# Doorbell.net
KiCad netlist of a schematic drawn in EAGLE
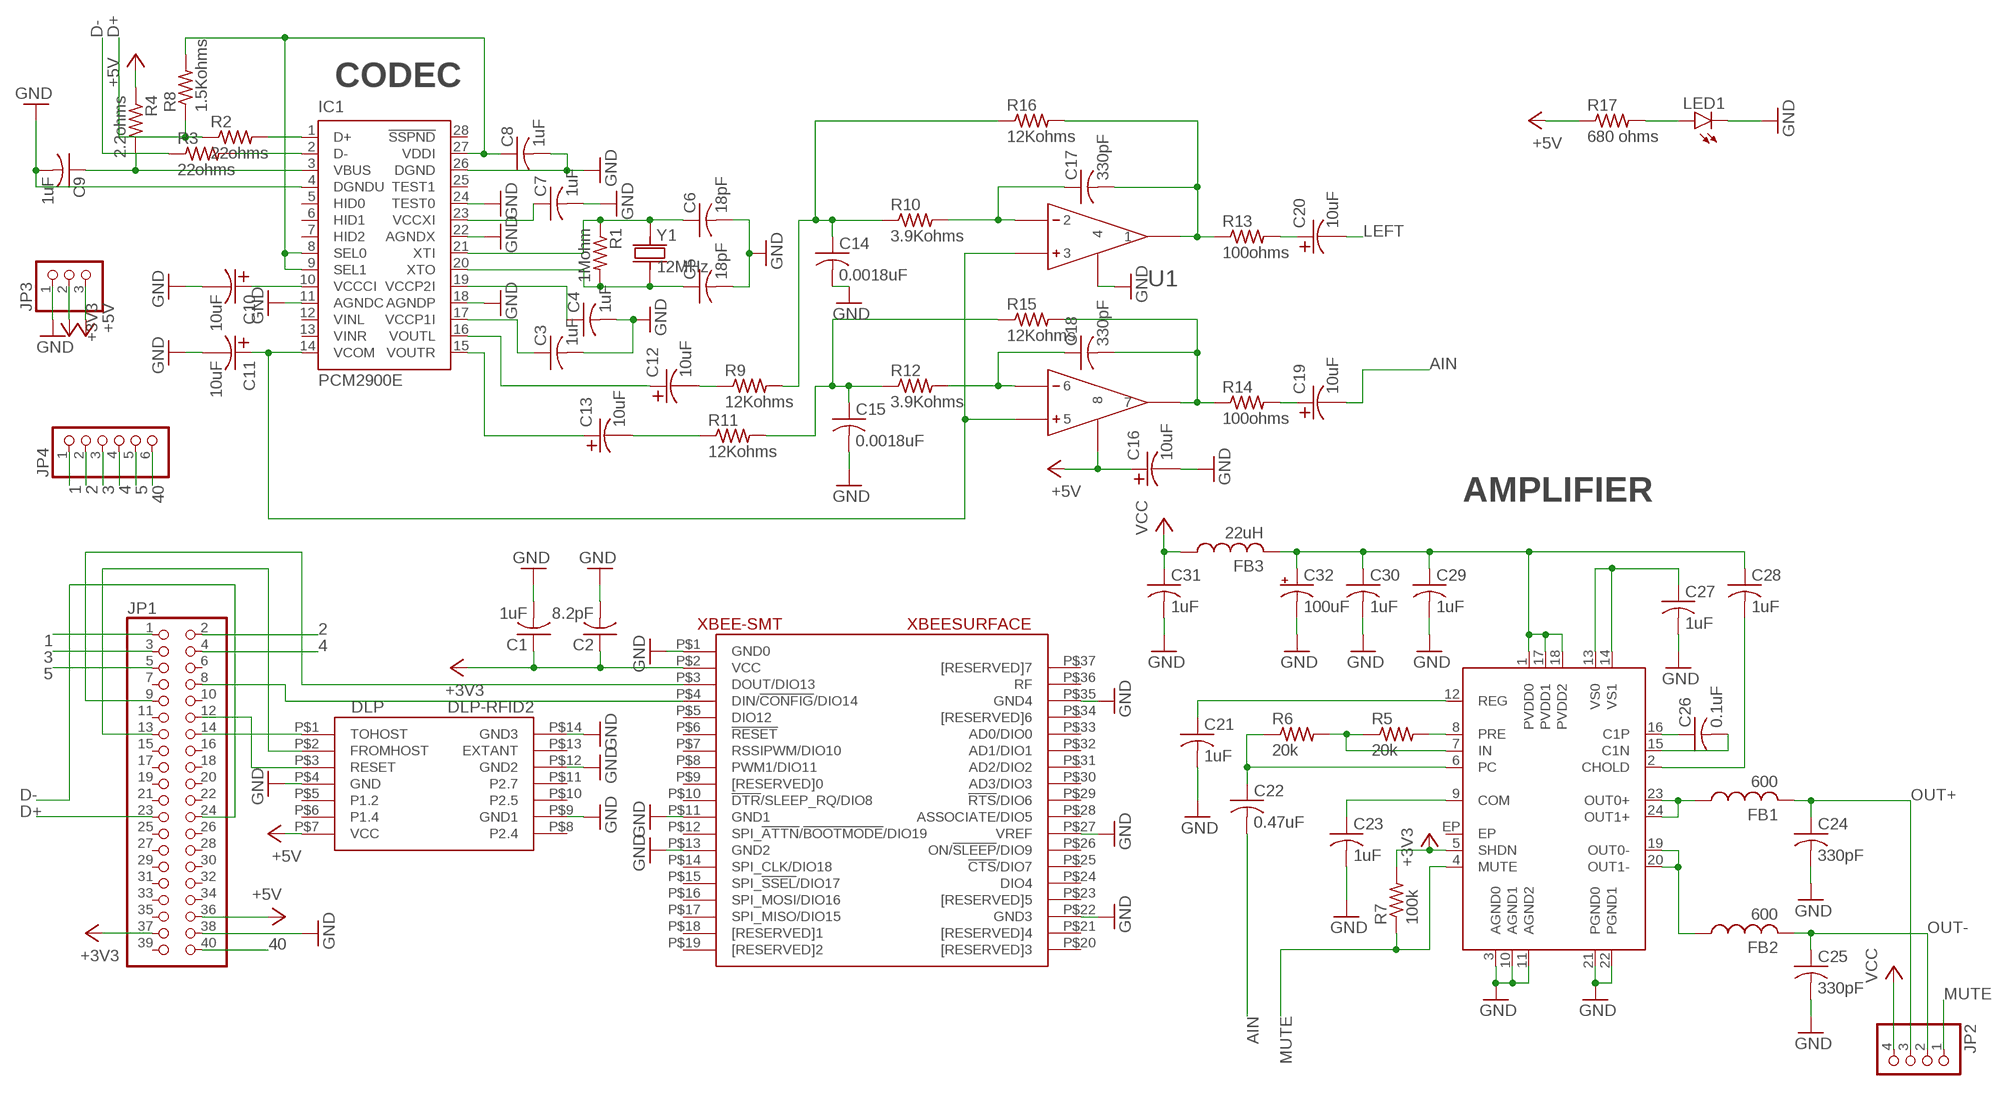
[diagram p0: schematic, sheet 1]

(export (version "E")
  (design (tool "Eeschema 10.0.6"))
  (components
    (comp (ref "C1")
      (value "1uF")
      (footprint "eagle-import:0603_CAP")
      (libsource (lib "eagle-import") (part "CAP0603"))
    )
    (comp (ref "C2")
      (value "8.2pF")
      (footprint "eagle-import:0603_CAP")
      (libsource (lib "eagle-import") (part "CAP0603"))
    )
    (comp (ref "C3")
      (value "1uF")
      (footprint "eagle-import:0603_CAP")
      (libsource (lib "eagle-import") (part "CAP0603"))
    )
    (comp (ref "C4")
      (value "1uF")
      (footprint "eagle-import:0603_CAP")
      (libsource (lib "eagle-import") (part "CAP0603"))
    )
    (comp (ref "C5")
      (value "18pF")
      (footprint "eagle-import:0603_CAP")
      (libsource (lib "eagle-import") (part "CAP0603"))
    )
    (comp (ref "C6")
      (value "18pF")
      (footprint "eagle-import:0603_CAP")
      (libsource (lib "eagle-import") (part "CAP0603"))
    )
    (comp (ref "C7")
      (value "1uF")
      (footprint "eagle-import:0603_CAP")
      (libsource (lib "eagle-import") (part "CAP0603"))
    )
    (comp (ref "C8")
      (value "1uF")
      (footprint "eagle-import:0603_CAP")
      (libsource (lib "eagle-import") (part "CAP0603"))
    )
    (comp (ref "C9")
      (value "1uF")
      (footprint "eagle-import:0603_CAP")
      (libsource (lib "eagle-import") (part "CAP0603"))
    )
    (comp (ref "C10")
      (value "10uF")
      (footprint "eagle-import:1411_CAP")
      (libsource (lib "eagle-import") (part "CAP-TANT"))
    )
    (comp (ref "C11")
      (value "10uF")
      (footprint "eagle-import:1411_CAP")
      (libsource (lib "eagle-import") (part "CAP-TANT"))
    )
    (comp (ref "C12")
      (value "10uF")
      (footprint "eagle-import:1411_CAP")
      (libsource (lib "eagle-import") (part "CAP-TANT"))
    )
    (comp (ref "C13")
      (value "10uF")
      (footprint "eagle-import:1411_CAP")
      (libsource (lib "eagle-import") (part "CAP-TANT"))
    )
    (comp (ref "C14")
      (value "0.0018uF")
      (footprint "eagle-import:0603_CAP")
      (libsource (lib "eagle-import") (part "CAP0603"))
    )
    (comp (ref "C15")
      (value "0.0018uF")
      (footprint "eagle-import:0603_CAP")
      (libsource (lib "eagle-import") (part "CAP0603"))
    )
    (comp (ref "C16")
      (value "10uF")
      (footprint "eagle-import:1411_CAP")
      (libsource (lib "eagle-import") (part "CAP-TANT"))
    )
    (comp (ref "C17")
      (value "330pF")
      (footprint "eagle-import:0603_CAP")
      (libsource (lib "eagle-import") (part "CAP0603"))
    )
    (comp (ref "C18")
      (value "330pF")
      (footprint "eagle-import:0603_CAP")
      (libsource (lib "eagle-import") (part "CAP0603"))
    )
    (comp (ref "C19")
      (value "10uF")
      (footprint "eagle-import:1411_CAP")
      (libsource (lib "eagle-import") (part "CAP-TANT"))
    )
    (comp (ref "C20")
      (value "10uF")
      (footprint "eagle-import:1411_CAP")
      (libsource (lib "eagle-import") (part "CAP-TANT"))
    )
    (comp (ref "C21")
      (value "1uF")
      (footprint "eagle-import:0603_CAP")
      (libsource (lib "eagle-import") (part "CAP0603"))
    )
    (comp (ref "C22")
      (value "0.47uF")
      (footprint "eagle-import:0603_CAP")
      (libsource (lib "eagle-import") (part "CAP0603"))
    )
    (comp (ref "C23")
      (value "1uF")
      (footprint "eagle-import:0603_CAP")
      (libsource (lib "eagle-import") (part "CAP0603"))
    )
    (comp (ref "C24")
      (value "330pF")
      (footprint "eagle-import:0603_CAP")
      (libsource (lib "eagle-import") (part "CAP0603"))
    )
    (comp (ref "C25")
      (value "330pF")
      (footprint "eagle-import:0603_CAP")
      (libsource (lib "eagle-import") (part "CAP0603"))
    )
    (comp (ref "C26")
      (value "0.1uF")
      (footprint "eagle-import:0603_CAP")
      (libsource (lib "eagle-import") (part "CAP0603"))
    )
    (comp (ref "C27")
      (value "1uF")
      (footprint "eagle-import:0603_CAP")
      (libsource (lib "eagle-import") (part "CAP0603"))
    )
    (comp (ref "C28")
      (value "1uF")
      (footprint "eagle-import:0603_CAP")
      (libsource (lib "eagle-import") (part "CAP0603"))
    )
    (comp (ref "C29")
      (value "1uF")
      (footprint "eagle-import:0603_CAP")
      (libsource (lib "eagle-import") (part "CAP0603"))
    )
    (comp (ref "C30")
      (value "1uF")
      (footprint "eagle-import:0603_CAP")
      (libsource (lib "eagle-import") (part "CAP0603"))
    )
    (comp (ref "C31")
      (value "1uF")
      (footprint "eagle-import:0603_CAP")
      (libsource (lib "eagle-import") (part "CAP0603"))
    )
    (comp (ref "C32")
      (value "100uF")
      (footprint "eagle-import:F_CAP")
      (libsource (lib "eagle-import") (part "CAP_POLF"))
    )
    (comp (ref "DLP")
      (value "DLP-RFID2")
      (footprint "eagle-import:DLP-RFID2")
      (libsource (lib "eagle-import") (part "DLP-RFID2"))
    )
    (comp (ref "FB1")
      (value "600")
      (footprint "eagle-import:0805_FB")
      (libsource (lib "eagle-import") (part "FB0805"))
    )
    (comp (ref "FB2")
      (value "600")
      (footprint "eagle-import:0805_FB")
      (libsource (lib "eagle-import") (part "FB0805"))
    )
    (comp (ref "FB3")
      (value "22uH")
      (footprint "eagle-import:0805_FB")
      (libsource (lib "eagle-import") (part "FB0805"))
    )
    (comp (ref "IC1")
      (value "PCM2900E")
      (footprint "eagle-import:SSOP28DB")
      (fields (field (name "MF") "TEXAS INSTRUMENTS"))
      (libsource (lib "eagle-import") (part "PCM2900E"))
    )
    (comp (ref "IC2")
      (value "MAX9737")
      (footprint "eagle-import:TQFN24")
      (fields (field (name "MANF") "Maxim"))
      (libsource (lib "eagle-import") (part "MAX9737"))
    )
    (comp (ref "JP1")
      (value "PINHD-2X20")
      (footprint "eagle-import:2X20")
      (libsource (lib "eagle-import") (part "PINHD-2X20"))
    )
    (comp (ref "JP2")
      (value "PINHD-1X4")
      (footprint "eagle-import:1X04")
      (libsource (lib "eagle-import") (part "PINHD-1X4"))
    )
    (comp (ref "JP3")
      (value "PINHD-1X3")
      (footprint "eagle-import:1X03")
      (libsource (lib "eagle-import") (part "PINHD-1X3"))
    )
    (comp (ref "JP4")
      (value "PINHD-1X6")
      (footprint "eagle-import:1X06")
      (libsource (lib "eagle-import") (part "PINHD-1X6"))
    )
    (comp (ref "LED1")
      (value "LED0603")
      (footprint "eagle-import:0603_LED")
      (fields (field (name "MANF") "Avago Technologies"))
      (libsource (lib "eagle-import") (part "LED0603"))
    )
    (comp (ref "R1")
      (value "1Mohm")
      (footprint "eagle-import:0603_RESISTOR")
      (libsource (lib "eagle-import") (part "RESISTOR0603"))
    )
    (comp (ref "R2")
      (value "22ohms")
      (footprint "eagle-import:0603_RESISTOR")
      (libsource (lib "eagle-import") (part "RESISTOR0603"))
    )
    (comp (ref "R3")
      (value "22ohms")
      (footprint "eagle-import:0603_RESISTOR")
      (libsource (lib "eagle-import") (part "RESISTOR0603"))
    )
    (comp (ref "R4")
      (value "2.2ohms")
      (footprint "eagle-import:0603_RESISTOR")
      (libsource (lib "eagle-import") (part "RESISTOR0603"))
    )
    (comp (ref "R5")
      (value "20k")
      (footprint "eagle-import:0603_RESISTOR")
      (libsource (lib "eagle-import") (part "RESISTOR0603"))
    )
    (comp (ref "R6")
      (value "20k")
      (footprint "eagle-import:0603_RESISTOR")
      (libsource (lib "eagle-import") (part "RESISTOR0603"))
    )
    (comp (ref "R7")
      (value "100k")
      (footprint "eagle-import:0603_RESISTOR")
      (libsource (lib "eagle-import") (part "RESISTOR0603"))
    )
    (comp (ref "R8")
      (value "1.5Kohms")
      (footprint "eagle-import:0603_RESISTOR")
      (libsource (lib "eagle-import") (part "RESISTOR0603"))
    )
    (comp (ref "R9")
      (value "12Kohms")
      (footprint "eagle-import:0603_RESISTOR")
      (libsource (lib "eagle-import") (part "RESISTOR0603"))
    )
    (comp (ref "R10")
      (value "3.9Kohms")
      (footprint "eagle-import:0603_RESISTOR")
      (libsource (lib "eagle-import") (part "RESISTOR0603"))
    )
    (comp (ref "R11")
      (value "12Kohms")
      (footprint "eagle-import:0603_RESISTOR")
      (libsource (lib "eagle-import") (part "RESISTOR0603"))
    )
    (comp (ref "R12")
      (value "3.9Kohms")
      (footprint "eagle-import:0603_RESISTOR")
      (libsource (lib "eagle-import") (part "RESISTOR0603"))
    )
    (comp (ref "R13")
      (value "100ohms")
      (footprint "eagle-import:0603_RESISTOR")
      (libsource (lib "eagle-import") (part "RESISTOR0603"))
    )
    (comp (ref "R14")
      (value "100ohms")
      (footprint "eagle-import:0603_RESISTOR")
      (libsource (lib "eagle-import") (part "RESISTOR0603"))
    )
    (comp (ref "R15")
      (value "12Kohms")
      (footprint "eagle-import:0603_RESISTOR")
      (libsource (lib "eagle-import") (part "RESISTOR0603"))
    )
    (comp (ref "R16")
      (value "12Kohms")
      (footprint "eagle-import:0603_RESISTOR")
      (libsource (lib "eagle-import") (part "RESISTOR0603"))
    )
    (comp (ref "R17")
      (value "680 ohms")
      (footprint "eagle-import:0603_RESISTOR")
      (libsource (lib "eagle-import") (part "RESISTOR0603"))
    )
    (comp (ref "U1")
      (value "OP-AMP")
      (footprint "eagle-import:OPA2353UA")
      (libsource (lib "eagle-import") (part "OP-AMP"))
    )
    (comp (ref "XBEE-SMT")
      (value "XBEESURFACE")
      (footprint "eagle-import:XBEESURFACE")
      (libsource (lib "eagle-import") (part "XBEESURFACE"))
    )
    (comp (ref "Y1")
      (value "12MHz")
      (footprint "eagle-import:CRYSTAL_5X3")
      (libsource (lib "eagle-import") (part "CRYSTAL5X3"))
    )
  )
  (nets
    (net (code "1") (name "+3V3") (class "Default")
      (node (ref "C1") (pin "1") (pinfunction "1_1") (pintype "passive"))
      (node (ref "C2") (pin "1") (pinfunction "1_1") (pintype "passive"))
      (node (ref "IC2") (pin "5") (pinfunction "SHDN_5") (pintype "input"))
      (node (ref "JP1") (pin "37") (pinfunction "37_37") (pintype "passive"))
      (node (ref "JP3") (pin "2") (pinfunction "2_2") (pintype "passive"))
      (node (ref "R7") (pin "2") (pinfunction "2_2") (pintype "passive"))
      (node (ref "XBEE-SMT") (pin "P$2") (pinfunction "VCC_P$2") (pintype "bidirectional"))
    )
    (net (code "2") (name "+5V") (class "Default")
      (node (ref "C16") (pin "P$1") (pinfunction "P$1_P$1") (pintype "passive"))
      (node (ref "DLP") (pin "P$7") (pinfunction "VCC_P$7") (pintype "bidirectional"))
      (node (ref "JP1") (pin "36") (pinfunction "36_36") (pintype "passive"))
      (node (ref "JP3") (pin "3") (pinfunction "3_3") (pintype "passive"))
      (node (ref "R17") (pin "1") (pinfunction "1_1") (pintype "passive"))
      (node (ref "R4") (pin "1") (pinfunction "1_1") (pintype "passive"))
      (node (ref "U1") (pin "P$8") (pinfunction "8_P$8") (pintype "bidirectional"))
    )
    (net (code "3") (name "/1") (class "Default")
      (node (ref "JP1") (pin "1") (pinfunction "1_1") (pintype "passive"))
      (node (ref "JP4") (pin "1") (pinfunction "1_1") (pintype "passive"))
    )
    (net (code "4") (name "/2") (class "Default")
      (node (ref "JP1") (pin "2") (pinfunction "2_2") (pintype "passive"))
      (node (ref "JP4") (pin "2") (pinfunction "2_2") (pintype "passive"))
    )
    (net (code "5") (name "/3") (class "Default")
      (node (ref "JP1") (pin "3") (pinfunction "3_3") (pintype "passive"))
      (node (ref "JP4") (pin "3") (pinfunction "3_3") (pintype "passive"))
    )
    (net (code "6") (name "/4") (class "Default")
      (node (ref "JP1") (pin "4") (pinfunction "4_4") (pintype "passive"))
      (node (ref "JP4") (pin "4") (pinfunction "4_4") (pintype "passive"))
    )
    (net (code "7") (name "/5") (class "Default")
      (node (ref "JP1") (pin "5") (pinfunction "5_5") (pintype "passive"))
      (node (ref "JP4") (pin "5") (pinfunction "5_5") (pintype "passive"))
    )
    (net (code "8") (name "/40") (class "Default")
      (node (ref "JP1") (pin "40") (pinfunction "40_40") (pintype "passive"))
      (node (ref "JP4") (pin "6") (pinfunction "6_6") (pintype "passive"))
    )
    (net (code "9") (name "/AIN") (class "Default")
      (node (ref "C19") (pin "P$2") (pinfunction "P$2_P$2") (pintype "passive"))
      (node (ref "C22") (pin "2") (pinfunction "2_2") (pintype "passive"))
    )
    (net (code "10") (name "/D+") (class "Default")
      (node (ref "JP1") (pin "23") (pinfunction "23_23") (pintype "passive"))
      (node (ref "R2") (pin "1") (pinfunction "1_1") (pintype "passive"))
      (node (ref "R8") (pin "1") (pinfunction "1_1") (pintype "passive"))
    )
    (net (code "11") (name "/D-") (class "Default")
      (node (ref "JP1") (pin "24") (pinfunction "24_24") (pintype "passive"))
      (node (ref "R3") (pin "1") (pinfunction "1_1") (pintype "passive"))
    )
    (net (code "12") (name "/LEFT") (class "Default")
      (node (ref "C20") (pin "P$2") (pinfunction "P$2_P$2") (pintype "passive"))
    )
    (net (code "13") (name "/MUTE") (class "Default")
      (node (ref "IC2") (pin "4") (pinfunction "MUTE_4") (pintype "input"))
      (node (ref "JP2") (pin "1") (pinfunction "1_1") (pintype "passive"))
      (node (ref "R7") (pin "1") (pinfunction "1_1") (pintype "passive"))
    )
    (net (code "14") (name "/OUT+") (class "Default")
      (node (ref "C24") (pin "1") (pinfunction "1_1") (pintype "passive"))
      (node (ref "FB1") (pin "2") (pinfunction "2_2") (pintype "passive"))
      (node (ref "JP2") (pin "3") (pinfunction "3_3") (pintype "passive"))
    )
    (net (code "15") (name "/OUT-") (class "Default")
      (node (ref "C25") (pin "1") (pinfunction "1_1") (pintype "passive"))
      (node (ref "FB2") (pin "2") (pinfunction "2_2") (pintype "passive"))
      (node (ref "JP2") (pin "2") (pinfunction "2_2") (pintype "passive"))
    )
    (net (code "16") (name "GND") (class "Default")
      (node (ref "C1") (pin "2") (pinfunction "2_2") (pintype "passive"))
      (node (ref "C10") (pin "P$2") (pinfunction "P$2_P$2") (pintype "passive"))
      (node (ref "C11") (pin "P$2") (pinfunction "P$2_P$2") (pintype "passive"))
      (node (ref "C14") (pin "2") (pinfunction "2_2") (pintype "passive"))
      (node (ref "C15") (pin "2") (pinfunction "2_2") (pintype "passive"))
      (node (ref "C16") (pin "P$2") (pinfunction "P$2_P$2") (pintype "passive"))
      (node (ref "C2") (pin "2") (pinfunction "2_2") (pintype "passive"))
      (node (ref "C21") (pin "2") (pinfunction "2_2") (pintype "passive"))
      (node (ref "C23") (pin "2") (pinfunction "2_2") (pintype "passive"))
      (node (ref "C24") (pin "2") (pinfunction "2_2") (pintype "passive"))
      (node (ref "C25") (pin "2") (pinfunction "2_2") (pintype "passive"))
      (node (ref "C27") (pin "2") (pinfunction "2_2") (pintype "passive"))
      (node (ref "C29") (pin "2") (pinfunction "2_2") (pintype "passive"))
      (node (ref "C3") (pin "2") (pinfunction "2_2") (pintype "passive"))
      (node (ref "C30") (pin "2") (pinfunction "2_2") (pintype "passive"))
      (node (ref "C31") (pin "2") (pinfunction "2_2") (pintype "passive"))
      (node (ref "C32") (pin "-") (pinfunction "-_-") (pintype "passive"))
      (node (ref "C4") (pin "2") (pinfunction "2_2") (pintype "passive"))
      (node (ref "C5") (pin "2") (pinfunction "2_2") (pintype "passive"))
      (node (ref "C6") (pin "2") (pinfunction "2_2") (pintype "passive"))
      (node (ref "C7") (pin "2") (pinfunction "2_2") (pintype "passive"))
      (node (ref "C8") (pin "2") (pinfunction "2_2") (pintype "passive"))
      (node (ref "C9") (pin "2") (pinfunction "2_2") (pintype "passive"))
      (node (ref "DLP") (pin "P$12") (pinfunction "GND2_P$12") (pintype "bidirectional"))
      (node (ref "DLP") (pin "P$14") (pinfunction "GND3_P$14") (pintype "bidirectional"))
      (node (ref "DLP") (pin "P$4") (pinfunction "GND_P$4") (pintype "bidirectional"))
      (node (ref "DLP") (pin "P$9") (pinfunction "GND1_P$9") (pintype "bidirectional"))
      (node (ref "IC1") (pin "11") (pinfunction "AGNDC_11") (pintype "power_in"))
      (node (ref "IC1") (pin "18") (pinfunction "AGNDP_18") (pintype "power_in"))
      (node (ref "IC1") (pin "22") (pinfunction "AGNDX_22") (pintype "power_in"))
      (node (ref "IC1") (pin "24") (pinfunction "TEST0_24") (pintype "input"))
      (node (ref "IC1") (pin "26") (pinfunction "DGND_26") (pintype "power_in"))
      (node (ref "IC1") (pin "4") (pinfunction "DGNDU_4") (pintype "power_in"))
      (node (ref "IC2") (pin "10") (pinfunction "AGND1_10") (pintype "power_in"))
      (node (ref "IC2") (pin "11") (pinfunction "AGND2_11") (pintype "power_in"))
      (node (ref "IC2") (pin "21") (pinfunction "PGND0_21") (pintype "power_in"))
      (node (ref "IC2") (pin "22") (pinfunction "PGND1_22") (pintype "power_in"))
      (node (ref "IC2") (pin "3") (pinfunction "AGND0_3") (pintype "power_in"))
      (node (ref "JP1") (pin "38") (pinfunction "38_38") (pintype "passive"))
      (node (ref "JP3") (pin "1") (pinfunction "1_1") (pintype "passive"))
      (node (ref "LED1") (pin "C") (pinfunction "C_C") (pintype "passive"))
      (node (ref "U1") (pin "P$4") (pinfunction "4_P$4") (pintype "bidirectional"))
      (node (ref "XBEE-SMT") (pin "P$1") (pinfunction "GND0_P$1") (pintype "bidirectional"))
      (node (ref "XBEE-SMT") (pin "P$11") (pinfunction "GND1_P$11") (pintype "bidirectional"))
      (node (ref "XBEE-SMT") (pin "P$13") (pinfunction "GND2_P$13") (pintype "bidirectional"))
      (node (ref "XBEE-SMT") (pin "P$22") (pinfunction "GND3_P$22") (pintype "bidirectional"))
      (node (ref "XBEE-SMT") (pin "P$27") (pinfunction "VREF_P$27") (pintype "bidirectional"))
      (node (ref "XBEE-SMT") (pin "P$35") (pinfunction "GND4_P$35") (pintype "bidirectional"))
    )
    (net (code "17") (name "Net-(C12-PadP$2)") (class "Default")
      (node (ref "C12") (pin "P$2") (pinfunction "P$2_P$2") (pintype "passive"))
      (node (ref "R9") (pin "1") (pinfunction "1_1") (pintype "passive"))
    )
    (net (code "18") (name "Net-(C13-PadP$2)") (class "Default")
      (node (ref "C13") (pin "P$2") (pinfunction "P$2_P$2") (pintype "passive"))
      (node (ref "R11") (pin "1") (pinfunction "1_1") (pintype "passive"))
    )
    (net (code "19") (name "Net-(C14-Pad1)") (class "Default")
      (node (ref "C14") (pin "1") (pinfunction "1_1") (pintype "passive"))
      (node (ref "R10") (pin "1") (pinfunction "1_1") (pintype "passive"))
      (node (ref "R16") (pin "1") (pinfunction "1_1") (pintype "passive"))
      (node (ref "R9") (pin "2") (pinfunction "2_2") (pintype "passive"))
    )
    (net (code "20") (name "Net-(C15-Pad1)") (class "Default")
      (node (ref "C15") (pin "1") (pinfunction "1_1") (pintype "passive"))
      (node (ref "R11") (pin "2") (pinfunction "2_2") (pintype "passive"))
      (node (ref "R12") (pin "1") (pinfunction "1_1") (pintype "passive"))
      (node (ref "R15") (pin "1") (pinfunction "1_1") (pintype "passive"))
    )
    (net (code "21") (name "Net-(C19-PadP$1)") (class "Default")
      (node (ref "C19") (pin "P$1") (pinfunction "P$1_P$1") (pintype "passive"))
      (node (ref "R14") (pin "2") (pinfunction "2_2") (pintype "passive"))
    )
    (net (code "22") (name "Net-(C20-PadP$1)") (class "Default")
      (node (ref "C20") (pin "P$1") (pinfunction "P$1_P$1") (pintype "passive"))
      (node (ref "R13") (pin "2") (pinfunction "2_2") (pintype "passive"))
    )
    (net (code "23") (name "Net-(DLP-FROMHOST)") (class "Default")
      (node (ref "DLP") (pin "P$2") (pinfunction "FROMHOST_P$2") (pintype "bidirectional"))
      (node (ref "JP1") (pin "13") (pinfunction "13_13") (pintype "passive"))
    )
    (net (code "24") (name "Net-(DLP-RESET)") (class "Default")
      (node (ref "DLP") (pin "P$3") (pinfunction "RESET_P$3") (pintype "bidirectional"))
      (node (ref "JP1") (pin "12") (pinfunction "12_12") (pintype "passive"))
    )
    (net (code "25") (name "Net-(DLP-TOHOST)") (class "Default")
      (node (ref "DLP") (pin "P$1") (pinfunction "TOHOST_P$1") (pintype "bidirectional"))
      (node (ref "JP1") (pin "14") (pinfunction "14_14") (pintype "passive"))
    )
    (net (code "26") (name "Net-(IC1-D+)") (class "Default")
      (node (ref "IC1") (pin "1") (pinfunction "D+_1") (pintype "bidirectional"))
      (node (ref "R2") (pin "2") (pinfunction "2_2") (pintype "passive"))
    )
    (net (code "27") (name "Net-(IC1-D-)") (class "Default")
      (node (ref "IC1") (pin "2") (pinfunction "D-_2") (pintype "bidirectional"))
      (node (ref "R3") (pin "2") (pinfunction "2_2") (pintype "passive"))
    )
    (net (code "28") (name "Net-(IC1-SEL0)") (class "Default")
      (node (ref "C8") (pin "1") (pinfunction "1_1") (pintype "passive"))
      (node (ref "IC1") (pin "27") (pinfunction "VDDI_27") (pintype "power_in"))
      (node (ref "IC1") (pin "8") (pinfunction "SEL0_8") (pintype "input"))
      (node (ref "IC1") (pin "9") (pinfunction "SEL1_9") (pintype "input"))
      (node (ref "R8") (pin "2") (pinfunction "2_2") (pintype "passive"))
    )
    (net (code "29") (name "Net-(IC1-VBUS)") (class "Default")
      (node (ref "C9") (pin "1") (pinfunction "1_1") (pintype "passive"))
      (node (ref "IC1") (pin "3") (pinfunction "VBUS_3") (pintype "power_in"))
      (node (ref "R4") (pin "2") (pinfunction "2_2") (pintype "passive"))
    )
    (net (code "30") (name "Net-(IC1-VCCCI)") (class "Default")
      (node (ref "C10") (pin "P$1") (pinfunction "P$1_P$1") (pintype "passive"))
      (node (ref "IC1") (pin "10") (pinfunction "VCCCI_10") (pintype "power_in"))
    )
    (net (code "31") (name "Net-(IC1-VCCP1I)") (class "Default")
      (node (ref "C3") (pin "1") (pinfunction "1_1") (pintype "passive"))
      (node (ref "IC1") (pin "17") (pinfunction "VCCP1I_17") (pintype "input"))
    )
    (net (code "32") (name "Net-(IC1-VCCP2I)") (class "Default")
      (node (ref "C4") (pin "1") (pinfunction "1_1") (pintype "passive"))
      (node (ref "IC1") (pin "19") (pinfunction "VCCP2I_19") (pintype "power_in"))
    )
    (net (code "33") (name "Net-(IC1-VCCXI)") (class "Default")
      (node (ref "C7") (pin "1") (pinfunction "1_1") (pintype "passive"))
      (node (ref "IC1") (pin "23") (pinfunction "VCCXI_23") (pintype "power_in"))
    )
    (net (code "34") (name "Net-(IC1-VCOM)") (class "Default")
      (node (ref "C11") (pin "P$1") (pinfunction "P$1_P$1") (pintype "passive"))
      (node (ref "IC1") (pin "14") (pinfunction "VCOM_14") (pintype "power_in"))
      (node (ref "U1") (pin "P$3") (pinfunction "3_P$3") (pintype "bidirectional"))
      (node (ref "U1") (pin "P$5") (pinfunction "5_P$5") (pintype "bidirectional"))
    )
    (net (code "35") (name "Net-(IC1-VOUTL)") (class "Default")
      (node (ref "C12") (pin "P$1") (pinfunction "P$1_P$1") (pintype "passive"))
      (node (ref "IC1") (pin "16") (pinfunction "VOUTL_16") (pintype "output"))
    )
    (net (code "36") (name "Net-(IC1-VOUTR)") (class "Default")
      (node (ref "C13") (pin "P$1") (pinfunction "P$1_P$1") (pintype "passive"))
      (node (ref "IC1") (pin "15") (pinfunction "VOUTR_15") (pintype "output"))
    )
    (net (code "37") (name "Net-(IC1-XTI)") (class "Default")
      (node (ref "C6") (pin "1") (pinfunction "1_1") (pintype "passive"))
      (node (ref "IC1") (pin "21") (pinfunction "XTI_21") (pintype "input"))
      (node (ref "R1") (pin "1") (pinfunction "1_1") (pintype "passive"))
      (node (ref "Y1") (pin "1") (pinfunction "1_1") (pintype "passive"))
    )
    (net (code "38") (name "Net-(IC1-XTO)") (class "Default")
      (node (ref "C5") (pin "1") (pinfunction "1_1") (pintype "passive"))
      (node (ref "IC1") (pin "20") (pinfunction "XTO_20") (pintype "output"))
      (node (ref "R1") (pin "2") (pinfunction "2_2") (pintype "passive"))
      (node (ref "Y1") (pin "2") (pinfunction "2_2") (pintype "passive"))
    )
    (net (code "39") (name "Net-(IC2-C1N)") (class "Default")
      (node (ref "C26") (pin "2") (pinfunction "2_2") (pintype "passive"))
      (node (ref "IC2") (pin "15") (pinfunction "C1N_15") (pintype "output"))
    )
    (net (code "40") (name "Net-(IC2-C1P)") (class "Default")
      (node (ref "C26") (pin "1") (pinfunction "1_1") (pintype "passive"))
      (node (ref "IC2") (pin "16") (pinfunction "C1P_16") (pintype "output"))
    )
    (net (code "41") (name "Net-(IC2-CHOLD)") (class "Default")
      (node (ref "C28") (pin "2") (pinfunction "2_2") (pintype "passive"))
      (node (ref "IC2") (pin "2") (pinfunction "CHOLD_2") (pintype "output"))
    )
    (net (code "42") (name "Net-(IC2-COM)") (class "Default")
      (node (ref "C23") (pin "1") (pinfunction "1_1") (pintype "passive"))
      (node (ref "IC2") (pin "9") (pinfunction "COM_9") (pintype "input"))
    )
    (net (code "43") (name "Net-(IC2-IN)") (class "Default")
      (node (ref "IC2") (pin "7") (pinfunction "IN_7") (pintype "input"))
      (node (ref "R5") (pin "1") (pinfunction "1_1") (pintype "passive"))
      (node (ref "R6") (pin "2") (pinfunction "2_2") (pintype "passive"))
    )
    (net (code "44") (name "Net-(IC2-OUT0+)") (class "Default")
      (node (ref "FB1") (pin "1") (pinfunction "1_1") (pintype "passive"))
      (node (ref "IC2") (pin "23") (pinfunction "OUT0+_23") (pintype "output"))
      (node (ref "IC2") (pin "24") (pinfunction "OUT1+_24") (pintype "output"))
    )
    (net (code "45") (name "Net-(IC2-OUT0-)") (class "Default")
      (node (ref "FB2") (pin "1") (pinfunction "1_1") (pintype "passive"))
      (node (ref "IC2") (pin "19") (pinfunction "OUT0-_19") (pintype "output"))
      (node (ref "IC2") (pin "20") (pinfunction "OUT1-_20") (pintype "output"))
    )
    (net (code "46") (name "Net-(IC2-PC)") (class "Default")
      (node (ref "C22") (pin "1") (pinfunction "1_1") (pintype "passive"))
      (node (ref "IC2") (pin "6") (pinfunction "PC_6") (pintype "input"))
      (node (ref "R6") (pin "1") (pinfunction "1_1") (pintype "passive"))
    )
    (net (code "47") (name "Net-(IC2-PRE)") (class "Default")
      (node (ref "IC2") (pin "8") (pinfunction "PRE_8") (pintype "output"))
      (node (ref "R5") (pin "2") (pinfunction "2_2") (pintype "passive"))
    )
    (net (code "48") (name "Net-(IC2-PVDD0)") (class "Default")
      (node (ref "C28") (pin "1") (pinfunction "1_1") (pintype "passive"))
      (node (ref "C29") (pin "1") (pinfunction "1_1") (pintype "passive"))
      (node (ref "C30") (pin "1") (pinfunction "1_1") (pintype "passive"))
      (node (ref "C32") (pin "+") (pinfunction "+_+") (pintype "passive"))
      (node (ref "FB3") (pin "2") (pinfunction "2_2") (pintype "passive"))
      (node (ref "IC2") (pin "1") (pinfunction "PVDD0_1") (pintype "power_in"))
      (node (ref "IC2") (pin "17") (pinfunction "PVDD1_17") (pintype "power_in"))
      (node (ref "IC2") (pin "18") (pinfunction "PVDD2_18") (pintype "power_in"))
    )
    (net (code "49") (name "Net-(IC2-REG)") (class "Default")
      (node (ref "C21") (pin "1") (pinfunction "1_1") (pintype "passive"))
      (node (ref "IC2") (pin "12") (pinfunction "REG_12") (pintype "output"))
    )
    (net (code "50") (name "Net-(IC2-VS0)") (class "Default")
      (node (ref "C27") (pin "1") (pinfunction "1_1") (pintype "passive"))
      (node (ref "IC2") (pin "13") (pinfunction "VS0_13") (pintype "output"))
      (node (ref "IC2") (pin "14") (pinfunction "VS1_14") (pintype "output"))
    )
    (net (code "51") (name "Net-(LED1-PadA)") (class "Default")
      (node (ref "LED1") (pin "A") (pinfunction "A_A") (pintype "passive"))
      (node (ref "R17") (pin "2") (pinfunction "2_2") (pintype "passive"))
    )
    (net (code "52") (name "Net-(U1-1)") (class "Default")
      (node (ref "C17") (pin "2") (pinfunction "2_2") (pintype "passive"))
      (node (ref "R13") (pin "1") (pinfunction "1_1") (pintype "passive"))
      (node (ref "R16") (pin "2") (pinfunction "2_2") (pintype "passive"))
      (node (ref "U1") (pin "P$1") (pinfunction "1_P$1") (pintype "bidirectional"))
    )
    (net (code "53") (name "Net-(U1-2)") (class "Default")
      (node (ref "C17") (pin "1") (pinfunction "1_1") (pintype "passive"))
      (node (ref "R10") (pin "2") (pinfunction "2_2") (pintype "passive"))
      (node (ref "U1") (pin "P$2") (pinfunction "2_P$2") (pintype "bidirectional"))
    )
    (net (code "54") (name "Net-(U1-6)") (class "Default")
      (node (ref "C18") (pin "1") (pinfunction "1_1") (pintype "passive"))
      (node (ref "R12") (pin "2") (pinfunction "2_2") (pintype "passive"))
      (node (ref "U1") (pin "P$6") (pinfunction "6_P$6") (pintype "bidirectional"))
    )
    (net (code "55") (name "Net-(U1-7)") (class "Default")
      (node (ref "C18") (pin "2") (pinfunction "2_2") (pintype "passive"))
      (node (ref "R14") (pin "1") (pinfunction "1_1") (pintype "passive"))
      (node (ref "R15") (pin "2") (pinfunction "2_2") (pintype "passive"))
      (node (ref "U1") (pin "P$7") (pinfunction "7_P$7") (pintype "bidirectional"))
    )
    (net (code "56") (name "Net-(XBEE-SMT-DIN{slash}~{CONFIG}{slash}DIO14)") (class "Default")
      (node (ref "JP1") (pin "8") (pinfunction "8_8") (pintype "passive"))
      (node (ref "XBEE-SMT") (pin "P$4") (pinfunction "DIN/~{CONFIG}/DIO14_P$4") (pintype "bidirectional"))
    )
    (net (code "57") (name "Net-(XBEE-SMT-DOUT{slash}DIO13)") (class "Default")
      (node (ref "JP1") (pin "9") (pinfunction "9_9") (pintype "passive"))
      (node (ref "XBEE-SMT") (pin "P$3") (pinfunction "DOUT/DIO13_P$3") (pintype "bidirectional"))
    )
    (net (code "58") (name "VCC") (class "Default")
      (node (ref "C31") (pin "1") (pinfunction "1_1") (pintype "passive"))
      (node (ref "FB3") (pin "1") (pinfunction "1_1") (pintype "passive"))
      (node (ref "JP2") (pin "4") (pinfunction "4_4") (pintype "passive"))
    )
    (net (code "59") (name "unconnected-(DLP-EXTANT-PadP$13)") (class "Default")
      (node (ref "DLP") (pin "P$13") (pinfunction "EXTANT_P$13") (pintype "bidirectional"))
    )
    (net (code "60") (name "unconnected-(DLP-P1.2-PadP$5)") (class "Default")
      (node (ref "DLP") (pin "P$5") (pinfunction "P1.2_P$5") (pintype "bidirectional"))
    )
    (net (code "61") (name "unconnected-(DLP-P1.4-PadP$6)") (class "Default")
      (node (ref "DLP") (pin "P$6") (pinfunction "P1.4_P$6") (pintype "bidirectional"))
    )
    (net (code "62") (name "unconnected-(DLP-P2.4-PadP$8)") (class "Default")
      (node (ref "DLP") (pin "P$8") (pinfunction "P2.4_P$8") (pintype "bidirectional"))
    )
    (net (code "63") (name "unconnected-(DLP-P2.5-PadP$10)") (class "Default")
      (node (ref "DLP") (pin "P$10") (pinfunction "P2.5_P$10") (pintype "bidirectional"))
    )
    (net (code "64") (name "unconnected-(DLP-P2.7-PadP$11)") (class "Default")
      (node (ref "DLP") (pin "P$11") (pinfunction "P2.7_P$11") (pintype "bidirectional"))
    )
    (net (code "65") (name "unconnected-(IC1-HID0-Pad5)") (class "Default")
      (node (ref "IC1") (pin "5") (pinfunction "HID0_5") (pintype "input"))
    )
    (net (code "66") (name "unconnected-(IC1-HID1-Pad6)") (class "Default")
      (node (ref "IC1") (pin "6") (pinfunction "HID1_6") (pintype "input"))
    )
    (net (code "67") (name "unconnected-(IC1-HID2-Pad7)") (class "Default")
      (node (ref "IC1") (pin "7") (pinfunction "HID2_7") (pintype "input"))
    )
    (net (code "68") (name "unconnected-(IC1-TEST1-Pad25)") (class "Default")
      (node (ref "IC1") (pin "25") (pinfunction "TEST1_25") (pintype "output"))
    )
    (net (code "69") (name "unconnected-(IC1-VINL-Pad12)") (class "Default")
      (node (ref "IC1") (pin "12") (pinfunction "VINL_12") (pintype "input"))
    )
    (net (code "70") (name "unconnected-(IC1-VINR-Pad13)") (class "Default")
      (node (ref "IC1") (pin "13") (pinfunction "VINR_13") (pintype "input"))
    )
    (net (code "71") (name "unconnected-(IC1-~{SSPND}-Pad28)") (class "Default")
      (node (ref "IC1") (pin "28") (pinfunction "~{SSPND}_28") (pintype "output"))
    )
    (net (code "72") (name "unconnected-(IC2-PadEP)") (class "Default")
      (node (ref "IC2") (pin "EP") (pinfunction "EP_EP") (pintype "passive"))
    )
    (net (code "73") (name "unconnected-(JP1-Pad6)") (class "Default")
      (node (ref "JP1") (pin "6") (pinfunction "6_6") (pintype "passive"))
    )
    (net (code "74") (name "unconnected-(JP1-Pad7)") (class "Default")
      (node (ref "JP1") (pin "7") (pinfunction "7_7") (pintype "passive"))
    )
    (net (code "75") (name "unconnected-(JP1-Pad10)") (class "Default")
      (node (ref "JP1") (pin "10") (pinfunction "10_10") (pintype "passive"))
    )
    (net (code "76") (name "unconnected-(JP1-Pad11)") (class "Default")
      (node (ref "JP1") (pin "11") (pinfunction "11_11") (pintype "passive"))
    )
    (net (code "77") (name "unconnected-(JP1-Pad15)") (class "Default")
      (node (ref "JP1") (pin "15") (pinfunction "15_15") (pintype "passive"))
    )
    (net (code "78") (name "unconnected-(JP1-Pad16)") (class "Default")
      (node (ref "JP1") (pin "16") (pinfunction "16_16") (pintype "passive"))
    )
    (net (code "79") (name "unconnected-(JP1-Pad17)") (class "Default")
      (node (ref "JP1") (pin "17") (pinfunction "17_17") (pintype "passive"))
    )
    (net (code "80") (name "unconnected-(JP1-Pad18)") (class "Default")
      (node (ref "JP1") (pin "18") (pinfunction "18_18") (pintype "passive"))
    )
    (net (code "81") (name "unconnected-(JP1-Pad19)") (class "Default")
      (node (ref "JP1") (pin "19") (pinfunction "19_19") (pintype "passive"))
    )
    (net (code "82") (name "unconnected-(JP1-Pad20)") (class "Default")
      (node (ref "JP1") (pin "20") (pinfunction "20_20") (pintype "passive"))
    )
    (net (code "83") (name "unconnected-(JP1-Pad21)") (class "Default")
      (node (ref "JP1") (pin "21") (pinfunction "21_21") (pintype "passive"))
    )
    (net (code "84") (name "unconnected-(JP1-Pad22)") (class "Default")
      (node (ref "JP1") (pin "22") (pinfunction "22_22") (pintype "passive"))
    )
    (net (code "85") (name "unconnected-(JP1-Pad25)") (class "Default")
      (node (ref "JP1") (pin "25") (pinfunction "25_25") (pintype "passive"))
    )
    (net (code "86") (name "unconnected-(JP1-Pad26)") (class "Default")
      (node (ref "JP1") (pin "26") (pinfunction "26_26") (pintype "passive"))
    )
    (net (code "87") (name "unconnected-(JP1-Pad27)") (class "Default")
      (node (ref "JP1") (pin "27") (pinfunction "27_27") (pintype "passive"))
    )
    (net (code "88") (name "unconnected-(JP1-Pad28)") (class "Default")
      (node (ref "JP1") (pin "28") (pinfunction "28_28") (pintype "passive"))
    )
    (net (code "89") (name "unconnected-(JP1-Pad29)") (class "Default")
      (node (ref "JP1") (pin "29") (pinfunction "29_29") (pintype "passive"))
    )
    (net (code "90") (name "unconnected-(JP1-Pad30)") (class "Default")
      (node (ref "JP1") (pin "30") (pinfunction "30_30") (pintype "passive"))
    )
    (net (code "91") (name "unconnected-(JP1-Pad31)") (class "Default")
      (node (ref "JP1") (pin "31") (pinfunction "31_31") (pintype "passive"))
    )
    (net (code "92") (name "unconnected-(JP1-Pad32)") (class "Default")
      (node (ref "JP1") (pin "32") (pinfunction "32_32") (pintype "passive"))
    )
    (net (code "93") (name "unconnected-(JP1-Pad33)") (class "Default")
      (node (ref "JP1") (pin "33") (pinfunction "33_33") (pintype "passive"))
    )
    (net (code "94") (name "unconnected-(JP1-Pad34)") (class "Default")
      (node (ref "JP1") (pin "34") (pinfunction "34_34") (pintype "passive"))
    )
    (net (code "95") (name "unconnected-(JP1-Pad35)") (class "Default")
      (node (ref "JP1") (pin "35") (pinfunction "35_35") (pintype "passive"))
    )
    (net (code "96") (name "unconnected-(JP1-Pad39)") (class "Default")
      (node (ref "JP1") (pin "39") (pinfunction "39_39") (pintype "passive"))
    )
    (net (code "97") (name "unconnected-(XBEE-SMT-AD0{slash}DIO0-PadP$33)") (class "Default")
      (node (ref "XBEE-SMT") (pin "P$33") (pinfunction "AD0/DIO0_P$33") (pintype "bidirectional"))
    )
    (net (code "98") (name "unconnected-(XBEE-SMT-AD1{slash}DIO1-PadP$32)") (class "Default")
      (node (ref "XBEE-SMT") (pin "P$32") (pinfunction "AD1/DIO1_P$32") (pintype "bidirectional"))
    )
    (net (code "99") (name "unconnected-(XBEE-SMT-AD2{slash}DIO2-PadP$31)") (class "Default")
      (node (ref "XBEE-SMT") (pin "P$31") (pinfunction "AD2/DIO2_P$31") (pintype "bidirectional"))
    )
    (net (code "100") (name "unconnected-(XBEE-SMT-AD3{slash}DIO3-PadP$30)") (class "Default")
      (node (ref "XBEE-SMT") (pin "P$30") (pinfunction "AD3/DIO3_P$30") (pintype "bidirectional"))
    )
    (net (code "101") (name "unconnected-(XBEE-SMT-ASSOCIATE{slash}DIO5-PadP$28)") (class "Default")
      (node (ref "XBEE-SMT") (pin "P$28") (pinfunction "ASSOCIATE/DIO5_P$28") (pintype "bidirectional"))
    )
    (net (code "102") (name "unconnected-(XBEE-SMT-DIO4-PadP$24)") (class "Default")
      (node (ref "XBEE-SMT") (pin "P$24") (pinfunction "DIO4_P$24") (pintype "bidirectional"))
    )
    (net (code "103") (name "unconnected-(XBEE-SMT-DIO12-PadP$5)") (class "Default")
      (node (ref "XBEE-SMT") (pin "P$5") (pinfunction "DIO12_P$5") (pintype "bidirectional"))
    )
    (net (code "104") (name "unconnected-(XBEE-SMT-ON{slash}~{SLEEP}{slash}DIO9-PadP$26)") (class "Default")
      (node (ref "XBEE-SMT") (pin "P$26") (pinfunction "ON/~{SLEEP}/DIO9_P$26") (pintype "bidirectional"))
    )
    (net (code "105") (name "unconnected-(XBEE-SMT-PWM1{slash}DIO11-PadP$8)") (class "Default")
      (node (ref "XBEE-SMT") (pin "P$8") (pinfunction "PWM1/DIO11_P$8") (pintype "bidirectional"))
    )
    (net (code "106") (name "unconnected-(XBEE-SMT-RF-PadP$36)") (class "Default")
      (node (ref "XBEE-SMT") (pin "P$36") (pinfunction "RF_P$36") (pintype "bidirectional"))
    )
    (net (code "107") (name "unconnected-(XBEE-SMT-RSSIPWM{slash}DIO10-PadP$7)") (class "Default")
      (node (ref "XBEE-SMT") (pin "P$7") (pinfunction "RSSIPWM/DIO10_P$7") (pintype "bidirectional"))
    )
    (net (code "108") (name "unconnected-(XBEE-SMT-SPI_CLK{slash}DIO18-PadP$14)") (class "Default")
      (node (ref "XBEE-SMT") (pin "P$14") (pinfunction "SPI_CLK/DIO18_P$14") (pintype "bidirectional"))
    )
    (net (code "109") (name "unconnected-(XBEE-SMT-SPI_MISO{slash}DIO15-PadP$17)") (class "Default")
      (node (ref "XBEE-SMT") (pin "P$17") (pinfunction "SPI_MISO/DIO15_P$17") (pintype "bidirectional"))
    )
    (net (code "110") (name "unconnected-(XBEE-SMT-SPI_MOSI{slash}DIO16-PadP$16)") (class "Default")
      (node (ref "XBEE-SMT") (pin "P$16") (pinfunction "SPI_MOSI/DIO16_P$16") (pintype "bidirectional"))
    )
    (net (code "111") (name "unconnected-(XBEE-SMT-SPI_~{ATTN}{slash}~{BOOTMODE}{slash}DIO19-PadP$12)") (class "Default")
      (node (ref "XBEE-SMT") (pin "P$12") (pinfunction "SPI_~{ATTN}/~{BOOTMODE}/DIO19_P$12") (pintype "bidirectional"))
    )
    (net (code "112") (name "unconnected-(XBEE-SMT-SPI_~{SSEL}{slash}DIO17-PadP$15)") (class "Default")
      (node (ref "XBEE-SMT") (pin "P$15") (pinfunction "SPI_~{SSEL}/DIO17_P$15") (pintype "bidirectional"))
    )
    (net (code "113") (name "unconnected-(XBEE-SMT-[RESERVED]0-PadP$9)") (class "Default")
      (node (ref "XBEE-SMT") (pin "P$9") (pinfunction "[RESERVED]0_P$9") (pintype "bidirectional"))
    )
    (net (code "114") (name "unconnected-(XBEE-SMT-[RESERVED]1-PadP$18)") (class "Default")
      (node (ref "XBEE-SMT") (pin "P$18") (pinfunction "[RESERVED]1_P$18") (pintype "bidirectional"))
    )
    (net (code "115") (name "unconnected-(XBEE-SMT-[RESERVED]2-PadP$19)") (class "Default")
      (node (ref "XBEE-SMT") (pin "P$19") (pinfunction "[RESERVED]2_P$19") (pintype "bidirectional"))
    )
    (net (code "116") (name "unconnected-(XBEE-SMT-[RESERVED]3-PadP$20)") (class "Default")
      (node (ref "XBEE-SMT") (pin "P$20") (pinfunction "[RESERVED]3_P$20") (pintype "bidirectional"))
    )
    (net (code "117") (name "unconnected-(XBEE-SMT-[RESERVED]4-PadP$21)") (class "Default")
      (node (ref "XBEE-SMT") (pin "P$21") (pinfunction "[RESERVED]4_P$21") (pintype "bidirectional"))
    )
    (net (code "118") (name "unconnected-(XBEE-SMT-[RESERVED]5-PadP$23)") (class "Default")
      (node (ref "XBEE-SMT") (pin "P$23") (pinfunction "[RESERVED]5_P$23") (pintype "bidirectional"))
    )
    (net (code "119") (name "unconnected-(XBEE-SMT-[RESERVED]6-PadP$34)") (class "Default")
      (node (ref "XBEE-SMT") (pin "P$34") (pinfunction "[RESERVED]6_P$34") (pintype "bidirectional"))
    )
    (net (code "120") (name "unconnected-(XBEE-SMT-[RESERVED]7-PadP$37)") (class "Default")
      (node (ref "XBEE-SMT") (pin "P$37") (pinfunction "[RESERVED]7_P$37") (pintype "bidirectional"))
    )
    (net (code "121") (name "unconnected-(XBEE-SMT-~{CTS}{slash}DIO7-PadP$25)") (class "Default")
      (node (ref "XBEE-SMT") (pin "P$25") (pinfunction "~{CTS}/DIO7_P$25") (pintype "bidirectional"))
    )
    (net (code "122") (name "unconnected-(XBEE-SMT-~{DTR}{slash}SLEEP_RQ{slash}DIO8-PadP$10)") (class "Default")
      (node (ref "XBEE-SMT") (pin "P$10") (pinfunction "~{DTR}/SLEEP_RQ/DIO8_P$10") (pintype "bidirectional"))
    )
    (net (code "123") (name "unconnected-(XBEE-SMT-~{RESET}-PadP$6)") (class "Default")
      (node (ref "XBEE-SMT") (pin "P$6") (pinfunction "~{RESET}_P$6") (pintype "bidirectional"))
    )
    (net (code "124") (name "unconnected-(XBEE-SMT-~{RTS}{slash}DIO6-PadP$29)") (class "Default")
      (node (ref "XBEE-SMT") (pin "P$29") (pinfunction "~{RTS}/DIO6_P$29") (pintype "bidirectional"))
    )
  )
)
